# Analog_System.net
KiCad netlist of a schematic drawn in Altium Designer
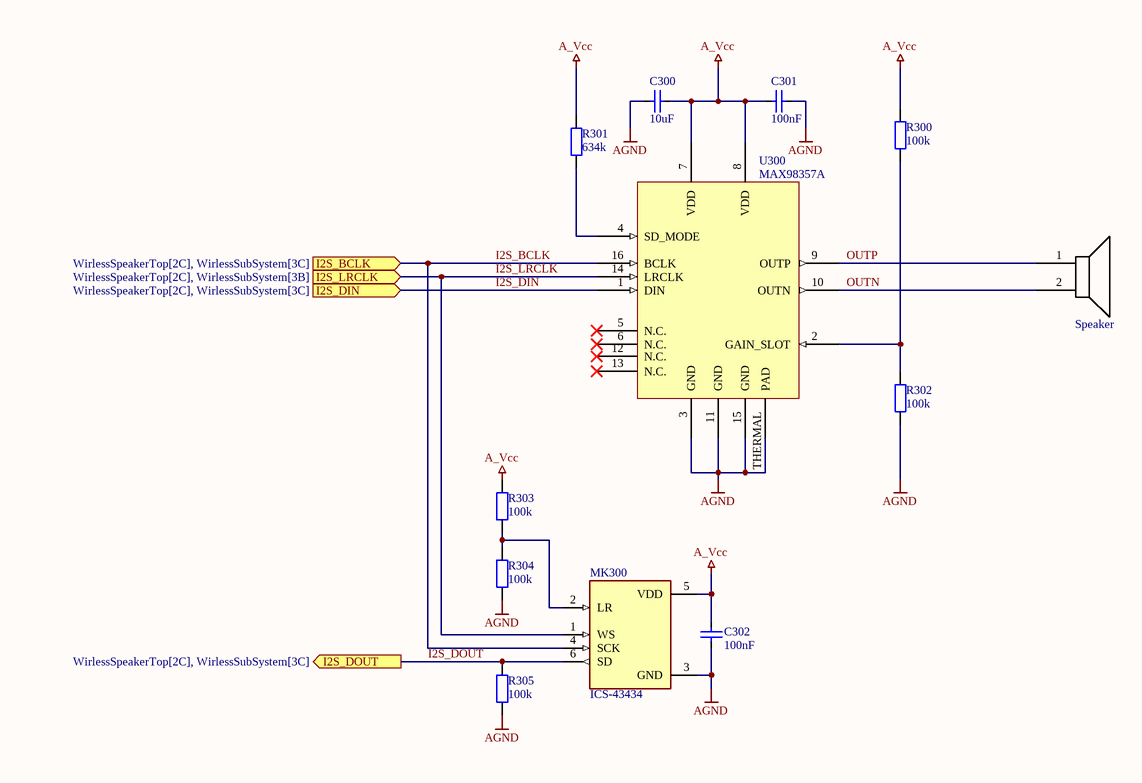
[diagram p0: Analog_System.SchDoc]

(export (version "E")
  (design (tool "Eeschema 10.0.6"))
  (components
    (comp (ref "C300")
      (value "10uF")
      (footprint "C-0603")
      (description "Multilayer Ceramic Capacitors MLCC")
      (fields (field (name "MANUFACTURER") "Murata Electronics") (field (name "MFR. PART NO.") "GRM18..."))
      (libsource (lib "WirelessAudioSpeaker") (part "C-SMD-0603"))
    )
    (comp (ref "C301")
      (value "100nF")
      (footprint "C-0603")
      (description "Multilayer Ceramic Capacitors MLCC")
      (fields (field (name "MANUFACTURER") "Murata Electronics") (field (name "MFR. PART NO.") "GRM18..."))
      (libsource (lib "WirelessAudioSpeaker") (part "C-SMD-0603"))
    )
    (comp (ref "C302")
      (value "100nF")
      (footprint "C-0603")
      (description "Multilayer Ceramic Capacitors MLCC")
      (fields (field (name "MANUFACTURER") "Murata Electronics") (field (name "MFR. PART NO.") "GRM18..."))
      (libsource (lib "WirelessAudioSpeaker") (part "C-SMD-0603"))
    )
    (comp (ref "MK300")
      (value "ICS-43434")
      (footprint "MK-ICS-43434")
      (description "Microphone MEMS\r\n60Hz ~ 20kHz Digital, I²S")
      (fields (field (name "MANUFACTURER") "TDK InvenSense"))
      (libsource (lib "WirelessAudioSpeaker") (part "MK-ICS-43434"))
    )
    (comp (ref "R300")
      (value "100k")
      (footprint "R-0603")
      (description "Thin Film Resistors - SMD  0.1W  1%")
      (fields (field (name "MFR. PART NO.") "MCU08050C*") (field (name "MANUFACTURER") "Vishay / Beyschlag"))
      (libsource (lib "WirelessAudioSpeaker") (part "R-SMD-0603"))
    )
    (comp (ref "R301")
      (value "634k")
      (footprint "R-0603")
      (description "Thin Film Resistors - SMD  0.1W  1%")
      (fields (field (name "MFR. PART NO.") "MCU08050C*") (field (name "MANUFACTURER") "Vishay / Beyschlag"))
      (libsource (lib "WirelessAudioSpeaker") (part "R-SMD-0603"))
    )
    (comp (ref "R302")
      (value "100k")
      (footprint "R-0603")
      (description "Thin Film Resistors - SMD  0.1W  1%")
      (fields (field (name "MFR. PART NO.") "MCU08050C*") (field (name "MANUFACTURER") "Vishay / Beyschlag"))
      (libsource (lib "WirelessAudioSpeaker") (part "R-SMD-0603"))
    )
    (comp (ref "R303")
      (value "100k")
      (footprint "R-0603")
      (description "Thin Film Resistors - SMD  0.1W  1%")
      (fields (field (name "MFR. PART NO.") "MCU08050C*") (field (name "MANUFACTURER") "Vishay / Beyschlag"))
      (libsource (lib "WirelessAudioSpeaker") (part "R-SMD-0603"))
    )
    (comp (ref "R304")
      (value "100k")
      (footprint "R-0603")
      (description "Thin Film Resistors - SMD  0.1W  1%")
      (fields (field (name "MFR. PART NO.") "MCU08050C*") (field (name "MANUFACTURER") "Vishay / Beyschlag"))
      (libsource (lib "WirelessAudioSpeaker") (part "R-SMD-0603"))
    )
    (comp (ref "R305")
      (value "100k")
      (footprint "R-0603")
      (description "Thin Film Resistors - SMD  0.1W  1%")
      (fields (field (name "MFR. PART NO.") "MCU08050C*") (field (name "MANUFACTURER") "Vishay / Beyschlag"))
      (libsource (lib "WirelessAudioSpeaker") (part "R-SMD-0603"))
    )
    (comp (ref "Speaker")
      (value "Speaker")
      (footprint "A-Speaker-Connector")
      (description "Speaker, 3W 8 Ohm")
      (libsource (lib "WirelessAudioSpeaker") (part "A_Speaker"))
    )
    (comp (ref "U300")
      (value "MAX98357A")
      (footprint "QFN16-3MM")
      (description "Tiny, Low-Cost, PCM Class D Amplifier")
      (fields
        (field (name "MANUFACTURER") "Maxim Integrated")
        (field (name "MFR. PART NO.") "MAX98357AETE+T")
      )
      (libsource (lib "WirelessAudioSpeaker") (part "U-MAX98357A"))
    )
  )
  (nets
    (net (code "1") (name "/I2S_BCLK") (class "Default")
      (node (ref "MK300") (pin "4") (pinfunction "SCK_4") (pintype "input"))
      (node (ref "U300") (pin "16") (pinfunction "BCLK_16") (pintype "input"))
    )
    (net (code "2") (name "/I2S_DIN") (class "Default")
      (node (ref "U300") (pin "1") (pinfunction "DIN_1") (pintype "input"))
    )
    (net (code "3") (name "/I2S_DOUT") (class "Default")
      (node (ref "MK300") (pin "6") (pinfunction "SD_6") (pintype "output"))
      (node (ref "R305") (pin "2") (pinfunction "2_2") (pintype "passive"))
    )
    (net (code "4") (name "/I2S_LRCLK") (class "Default")
      (node (ref "MK300") (pin "1") (pinfunction "WS_1") (pintype "input"))
      (node (ref "U300") (pin "14") (pinfunction "LRCLK_14") (pintype "input"))
    )
    (net (code "5") (name "/OUTN") (class "Default")
      (node (ref "Speaker") (pin "2") (pinfunction "2_2") (pintype "passive"))
      (node (ref "U300") (pin "10") (pinfunction "OUTN_10") (pintype "output"))
    )
    (net (code "6") (name "/OUTP") (class "Default")
      (node (ref "Speaker") (pin "1") (pinfunction "1_1") (pintype "passive"))
      (node (ref "U300") (pin "9") (pinfunction "OUTP_9") (pintype "output"))
    )
    (net (code "7") (name "AGND") (class "Default")
      (node (ref "C300") (pin "1") (pinfunction "1_1") (pintype "passive"))
      (node (ref "C301") (pin "2") (pinfunction "2_2") (pintype "passive"))
      (node (ref "C302") (pin "1") (pinfunction "1_1") (pintype "passive"))
      (node (ref "MK300") (pin "3") (pinfunction "GND_3") (pintype "power_in"))
      (node (ref "R302") (pin "1") (pinfunction "1_1") (pintype "passive"))
      (node (ref "R304") (pin "1") (pinfunction "1_1") (pintype "passive"))
      (node (ref "R305") (pin "1") (pinfunction "1_1") (pintype "passive"))
      (node (ref "U300") (pin "11") (pinfunction "GND_11") (pintype "power_in"))
      (node (ref "U300") (pin "15") (pinfunction "GND_15") (pintype "power_in"))
      (node (ref "U300") (pin "3") (pinfunction "GND_3") (pintype "power_in"))
      (node (ref "U300") (pin "THERMAL") (pinfunction "PAD_THERMAL") (pintype "power_in"))
    )
    (net (code "8") (name "A_Vcc") (class "Default")
      (node (ref "C300") (pin "2") (pinfunction "2_2") (pintype "passive"))
      (node (ref "C301") (pin "1") (pinfunction "1_1") (pintype "passive"))
      (node (ref "C302") (pin "2") (pinfunction "2_2") (pintype "passive"))
      (node (ref "MK300") (pin "5") (pinfunction "VDD_5") (pintype "power_in"))
      (node (ref "R300") (pin "2") (pinfunction "2_2") (pintype "passive"))
      (node (ref "R301") (pin "2") (pinfunction "2_2") (pintype "passive"))
      (node (ref "R303") (pin "2") (pinfunction "2_2") (pintype "passive"))
      (node (ref "U300") (pin "7") (pinfunction "VDD_7") (pintype "power_in"))
      (node (ref "U300") (pin "8") (pinfunction "VDD_8") (pintype "power_in"))
    )
    (net (code "9") (name "Net-(MK300-LR)") (class "Default")
      (node (ref "MK300") (pin "2") (pinfunction "LR_2") (pintype "input"))
      (node (ref "R303") (pin "1") (pinfunction "1_1") (pintype "passive"))
      (node (ref "R304") (pin "2") (pinfunction "2_2") (pintype "passive"))
    )
    (net (code "10") (name "Net-(U300-GAIN_SLOT)") (class "Default")
      (node (ref "R300") (pin "1") (pinfunction "1_1") (pintype "passive"))
      (node (ref "R302") (pin "2") (pinfunction "2_2") (pintype "passive"))
      (node (ref "U300") (pin "2") (pinfunction "GAIN_SLOT_2") (pintype "input"))
    )
    (net (code "11") (name "Net-(U300-SD_MODE)") (class "Default")
      (node (ref "R301") (pin "1") (pinfunction "1_1") (pintype "passive"))
      (node (ref "U300") (pin "4") (pinfunction "SD_MODE_4") (pintype "input"))
    )
    (net (code "12") (name "unconnected-(U300-N.C.-Pad5)") (class "Default")
      (node (ref "U300") (pin "5") (pinfunction "N.C._5") (pintype "passive+no_connect"))
    )
    (net (code "13") (name "unconnected-(U300-N.C.-Pad6)") (class "Default")
      (node (ref "U300") (pin "6") (pinfunction "N.C._6") (pintype "passive+no_connect"))
    )
    (net (code "14") (name "unconnected-(U300-N.C.-Pad12)") (class "Default")
      (node (ref "U300") (pin "12") (pinfunction "N.C._12") (pintype "passive+no_connect"))
    )
    (net (code "15") (name "unconnected-(U300-N.C.-Pad13)") (class "Default")
      (node (ref "U300") (pin "13") (pinfunction "N.C._13") (pintype "passive+no_connect"))
    )
  )
)
